# board.net
KiCad netlist of a schematic drawn in EAGLE
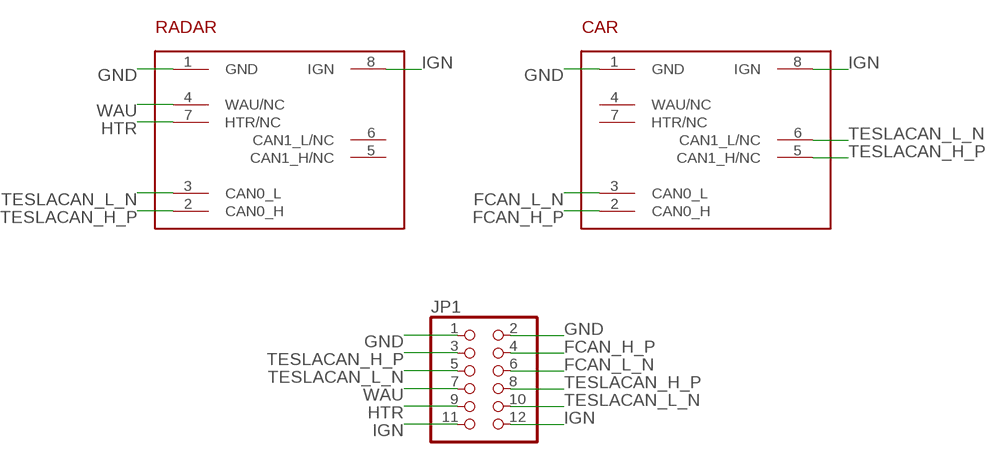
[diagram p0: schematic, sheet 1]

(export (version "E")
  (design (tool "Eeschema 10.0.6"))
  (components
    (comp (ref "CAR")
      (value "TE_AMP_1-967658-1")
      (footprint "eagle-import:TE_AMP_1-967658-1")
      (libsource (lib "eagle-import") (part "TE_AMP_1-967658-1"))
    )
    (comp (ref "JP1")
      (value "PINHD-2X6/90")
      (footprint "eagle-import:2X06_90")
      (libsource (lib "eagle-import") (part "PINHD-2X6/90"))
    )
    (comp (ref "RADAR")
      (value "TE_AMP_1-1534229-1TESLARADAR")
      (footprint "eagle-import:TE_AMP_1-1534229-1")
      (libsource (lib "eagle-import") (part "TE_AMP_1-1534229-1TESLARADAR"))
    )
  )
  (nets
    (net (code "1") (name "/FCAN_H_P") (class "Default")
      (node (ref "CAR") (pin "2") (pinfunction "CAN0_H_2") (pintype "bidirectional"))
      (node (ref "JP1") (pin "4") (pinfunction "4_4") (pintype "passive"))
    )
    (net (code "2") (name "/FCAN_L_N") (class "Default")
      (node (ref "CAR") (pin "3") (pinfunction "CAN0_L_3") (pintype "bidirectional"))
      (node (ref "JP1") (pin "6") (pinfunction "6_6") (pintype "passive"))
    )
    (net (code "3") (name "/GND") (class "Default")
      (node (ref "CAR") (pin "1") (pinfunction "GND_1") (pintype "power_in"))
      (node (ref "JP1") (pin "1") (pinfunction "1_1") (pintype "passive"))
      (node (ref "JP1") (pin "2") (pinfunction "2_2") (pintype "passive"))
      (node (ref "RADAR") (pin "1") (pinfunction "GND_1") (pintype "power_in"))
    )
    (net (code "4") (name "/HTR") (class "Default")
      (node (ref "JP1") (pin "9") (pinfunction "9_9") (pintype "passive"))
      (node (ref "RADAR") (pin "7") (pinfunction "HTR/NC_7") (pintype "bidirectional"))
    )
    (net (code "5") (name "/IGN") (class "Default")
      (node (ref "CAR") (pin "8") (pinfunction "IGN_8") (pintype "power_in"))
      (node (ref "JP1") (pin "11") (pinfunction "11_11") (pintype "passive"))
      (node (ref "JP1") (pin "12") (pinfunction "12_12") (pintype "passive"))
      (node (ref "RADAR") (pin "8") (pinfunction "IGN_8") (pintype "power_in"))
    )
    (net (code "6") (name "/TESLACAN_H_P") (class "Default")
      (node (ref "CAR") (pin "5") (pinfunction "CAN1_H/NC_5") (pintype "bidirectional"))
      (node (ref "JP1") (pin "3") (pinfunction "3_3") (pintype "passive"))
      (node (ref "JP1") (pin "8") (pinfunction "8_8") (pintype "passive"))
      (node (ref "RADAR") (pin "2") (pinfunction "CAN0_H_2") (pintype "bidirectional"))
    )
    (net (code "7") (name "/TESLACAN_L_N") (class "Default")
      (node (ref "CAR") (pin "6") (pinfunction "CAN1_L/NC_6") (pintype "bidirectional"))
      (node (ref "JP1") (pin "10") (pinfunction "10_10") (pintype "passive"))
      (node (ref "JP1") (pin "5") (pinfunction "5_5") (pintype "passive"))
      (node (ref "RADAR") (pin "3") (pinfunction "CAN0_L_3") (pintype "bidirectional"))
    )
    (net (code "8") (name "/WAU") (class "Default")
      (node (ref "JP1") (pin "7") (pinfunction "7_7") (pintype "passive"))
      (node (ref "RADAR") (pin "4") (pinfunction "WAU/NC_4") (pintype "bidirectional"))
    )
    (net (code "9") (name "unconnected-(CAR-HTR{slash}NC-Pad7)") (class "Default")
      (node (ref "CAR") (pin "7") (pinfunction "HTR/NC_7") (pintype "bidirectional"))
    )
    (net (code "10") (name "unconnected-(CAR-WAU{slash}NC-Pad4)") (class "Default")
      (node (ref "CAR") (pin "4") (pinfunction "WAU/NC_4") (pintype "bidirectional"))
    )
    (net (code "11") (name "unconnected-(RADAR-CAN1_H{slash}NC-Pad5)") (class "Default")
      (node (ref "RADAR") (pin "5") (pinfunction "CAN1_H/NC_5") (pintype "bidirectional"))
    )
    (net (code "12") (name "unconnected-(RADAR-CAN1_L{slash}NC-Pad6)") (class "Default")
      (node (ref "RADAR") (pin "6") (pinfunction "CAN1_L/NC_6") (pintype "bidirectional"))
    )
  )
)
